# ultrasonic_send.net
KiCad netlist of a schematic drawn in EAGLE
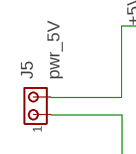
[diagram p0: schematic, sheet 1, part 1 of 2]
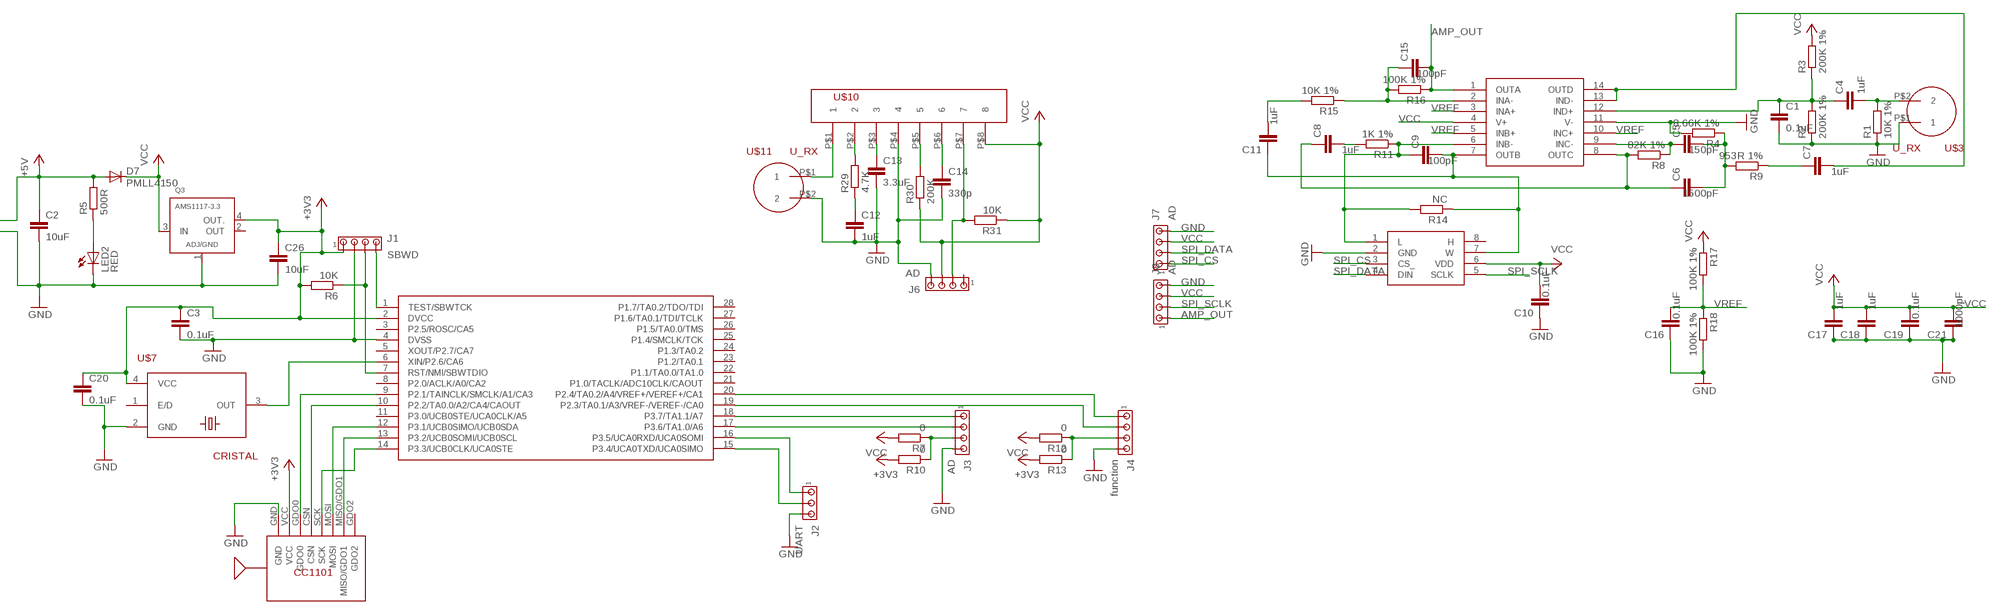
[diagram p1: schematic, sheet 1, part 2 of 2]

(export (version "E")
  (design (tool "Eeschema 10.0.6"))
  (components
    (comp (ref "C1")
      (value "0.1uF")
      (footprint "eagle-import:C0805")
      (libsource (lib "eagle-import") (part "C-EUC0805"))
    )
    (comp (ref "C2")
      (value "10uF")
      (footprint "eagle-import:C0805")
      (libsource (lib "eagle-import") (part "C-EUC0805"))
    )
    (comp (ref "C3")
      (value "0.1uF")
      (footprint "eagle-import:C0805")
      (libsource (lib "eagle-import") (part "C-EUC0805"))
    )
    (comp (ref "C4")
      (value "1uF")
      (footprint "eagle-import:C0805")
      (libsource (lib "eagle-import") (part "C-EUC0805"))
    )
    (comp (ref "C5")
      (value "150pF")
      (footprint "eagle-import:C0805")
      (libsource (lib "eagle-import") (part "C-EUC0805"))
    )
    (comp (ref "C6")
      (value "1500pF")
      (footprint "eagle-import:C0805")
      (libsource (lib "eagle-import") (part "C-EUC0805"))
    )
    (comp (ref "C7")
      (value "1uF")
      (footprint "eagle-import:C0805")
      (libsource (lib "eagle-import") (part "C-EUC0805"))
    )
    (comp (ref "C8")
      (value "1uF")
      (footprint "eagle-import:C0805")
      (libsource (lib "eagle-import") (part "C-EUC0805"))
    )
    (comp (ref "C9")
      (value "100pF")
      (footprint "eagle-import:C0805")
      (libsource (lib "eagle-import") (part "C-EUC0805"))
    )
    (comp (ref "C10")
      (value "0.1uF")
      (footprint "eagle-import:C0805")
      (libsource (lib "eagle-import") (part "C-EUC0805"))
    )
    (comp (ref "C11")
      (value "1uF")
      (footprint "eagle-import:C0805")
      (libsource (lib "eagle-import") (part "C-EUC0805"))
    )
    (comp (ref "C12")
      (value "1uF")
      (footprint "eagle-import:C0805")
      (libsource (lib "eagle-import") (part "C-EUC0805"))
    )
    (comp (ref "C13")
      (value "3.3uF")
      (footprint "eagle-import:C0805")
      (libsource (lib "eagle-import") (part "C-EUC0805"))
    )
    (comp (ref "C14")
      (value "330p")
      (footprint "eagle-import:C0805")
      (libsource (lib "eagle-import") (part "C-EUC0805"))
    )
    (comp (ref "C15")
      (value "100pF")
      (footprint "eagle-import:C0805")
      (libsource (lib "eagle-import") (part "C-EUC0805"))
    )
    (comp (ref "C16")
      (value "0.1uF")
      (footprint "eagle-import:C0805")
      (libsource (lib "eagle-import") (part "C-EUC0805"))
    )
    (comp (ref "C17")
      (value "1uF")
      (footprint "eagle-import:C0805")
      (libsource (lib "eagle-import") (part "C-EUC0805"))
    )
    (comp (ref "C18")
      (value "1uF")
      (footprint "eagle-import:C0805")
      (libsource (lib "eagle-import") (part "C-EUC0805"))
    )
    (comp (ref "C19")
      (value "0.1uF")
      (footprint "eagle-import:C0805")
      (libsource (lib "eagle-import") (part "C-EUC0805"))
    )
    (comp (ref "C20")
      (value "0.1uF")
      (footprint "eagle-import:C0805")
      (libsource (lib "eagle-import") (part "C-EUC0805"))
    )
    (comp (ref "C21")
      (value "1000pF")
      (footprint "eagle-import:C0805")
      (libsource (lib "eagle-import") (part "C-EUC0805"))
    )
    (comp (ref "C26")
      (value "10uF")
      (footprint "eagle-import:C0805")
      (libsource (lib "eagle-import") (part "C-EUC0805"))
    )
    (comp (ref "D7")
      (value "PMLL4150")
      (footprint "eagle-import:SOD80C")
      (libsource (lib "eagle-import") (part "PMLL4150"))
    )
    (comp (ref "J1")
      (value "SBWD")
      (footprint "eagle-import:10X04MTA")
      (libsource (lib "eagle-import") (part "MTA04-100"))
    )
    (comp (ref "J2")
      (value "UART")
      (footprint "eagle-import:10X03MTA")
      (libsource (lib "eagle-import") (part "MTA03-100"))
    )
    (comp (ref "J3")
      (value "AD")
      (footprint "eagle-import:10X04MTA")
      (libsource (lib "eagle-import") (part "MTA04-100"))
    )
    (comp (ref "J4")
      (value "function")
      (footprint "eagle-import:10X04MTA")
      (libsource (lib "eagle-import") (part "MTA04-100"))
    )
    (comp (ref "J5")
      (value "pwr_5V")
      (footprint "eagle-import:10X02MTA")
      (libsource (lib "eagle-import") (part "MTA02-100"))
    )
    (comp (ref "J6")
      (value "AD")
      (footprint "eagle-import:10X04MTA")
      (libsource (lib "eagle-import") (part "MTA04-100"))
    )
    (comp (ref "J7")
      (value "AD")
      (footprint "eagle-import:10X04MTA")
      (libsource (lib "eagle-import") (part "MTA04-100"))
    )
    (comp (ref "J8")
      (value "AD")
      (footprint "eagle-import:10X04MTA")
      (libsource (lib "eagle-import") (part "MTA04-100"))
    )
    (comp (ref "LED2")
      (value "RED")
      (footprint "eagle-import:SML0805")
      (libsource (lib "eagle-import") (part "LEDSML0805"))
    )
    (comp (ref "Q3")
      (value "AMS1117-3.3")
      (footprint "eagle-import:SOT223-4")
      (libsource (lib "eagle-import") (part "TLV1117"))
    )
    (comp (ref "R1")
      (value "10K 1%")
      (footprint "eagle-import:R0603")
      (libsource (lib "eagle-import") (part "R-EU_R0603"))
    )
    (comp (ref "R2")
      (value "200K 1%")
      (footprint "eagle-import:R0603")
      (libsource (lib "eagle-import") (part "R-EU_R0603"))
    )
    (comp (ref "R3")
      (value "200K 1%")
      (footprint "eagle-import:R0603")
      (libsource (lib "eagle-import") (part "R-EU_R0603"))
    )
    (comp (ref "R4")
      (value "8.66K 1%")
      (footprint "eagle-import:R0603")
      (libsource (lib "eagle-import") (part "R-EU_R0603"))
    )
    (comp (ref "R5")
      (value "500R")
      (footprint "eagle-import:R0603")
      (libsource (lib "eagle-import") (part "R-EU_R0603"))
    )
    (comp (ref "R6")
      (value "10K")
      (footprint "eagle-import:R0603")
      (libsource (lib "eagle-import") (part "R-EU_R0603"))
    )
    (comp (ref "R7")
      (value "0")
      (footprint "eagle-import:R0603")
      (libsource (lib "eagle-import") (part "R-EU_R0603"))
    )
    (comp (ref "R8")
      (value "82K 1%")
      (footprint "eagle-import:R0603")
      (libsource (lib "eagle-import") (part "R-EU_R0603"))
    )
    (comp (ref "R9")
      (value "953R 1%")
      (footprint "eagle-import:R0603")
      (libsource (lib "eagle-import") (part "R-EU_R0603"))
    )
    (comp (ref "R10")
      (value "0")
      (footprint "eagle-import:R0603")
      (libsource (lib "eagle-import") (part "R-EU_R0603"))
    )
    (comp (ref "R11")
      (value "1K 1%")
      (footprint "eagle-import:R0603")
      (libsource (lib "eagle-import") (part "R-EU_R0603"))
    )
    (comp (ref "R12")
      (value "0")
      (footprint "eagle-import:R0603")
      (libsource (lib "eagle-import") (part "R-EU_R0603"))
    )
    (comp (ref "R13")
      (value "0")
      (footprint "eagle-import:R0603")
      (libsource (lib "eagle-import") (part "R-EU_R0603"))
    )
    (comp (ref "R14")
      (value "NC")
      (footprint "eagle-import:R0603")
      (libsource (lib "eagle-import") (part "R-EU_R0603"))
    )
    (comp (ref "R15")
      (value "10K 1%")
      (footprint "eagle-import:R0603")
      (libsource (lib "eagle-import") (part "R-EU_R0603"))
    )
    (comp (ref "R16")
      (value "100K 1%")
      (footprint "eagle-import:R0603")
      (libsource (lib "eagle-import") (part "R-EU_R0603"))
    )
    (comp (ref "R17")
      (value "100K 1%")
      (footprint "eagle-import:R0603")
      (libsource (lib "eagle-import") (part "R-EU_R0603"))
    )
    (comp (ref "R18")
      (value "100K 1%")
      (footprint "eagle-import:R0603")
      (libsource (lib "eagle-import") (part "R-EU_R0603"))
    )
    (comp (ref "R29")
      (value "4.7K")
      (footprint "eagle-import:R0603")
      (libsource (lib "eagle-import") (part "R-EU_R0603"))
    )
    (comp (ref "R30")
      (value "200K")
      (footprint "eagle-import:R0603")
      (libsource (lib "eagle-import") (part "R-EU_R0603"))
    )
    (comp (ref "R31")
      (value "10K")
      (footprint "eagle-import:R0603")
      (libsource (lib "eagle-import") (part "R-EU_R0603"))
    )
    (comp (ref "U$1")
      (value "OPA1654PW")
      (footprint "eagle-import:D_R-PDSO-G14")
      (libsource (lib "eagle-import") (part "OPA1654PW"))
    )
    (comp (ref "U$2")
      (value "MSP430F2112")
      (footprint "eagle-import:PW_R-PDSO-G28")
      (libsource (lib "eagle-import") (part "MSP430F2112"))
    )
    (comp (ref "U$3")
      (value "U_RX")
      (footprint "eagle-import:ULTRASONIC")
      (libsource (lib "eagle-import") (part "ULTRASONIC"))
    )
    (comp (ref "U$4")
      (value "CC1101")
      (footprint "eagle-import:CC1101")
      (libsource (lib "eagle-import") (part "CC1101"))
    )
    (comp (ref "U$5")
      (value "MAX5401EKA-T")
      (footprint "eagle-import:SO08")
      (libsource (lib "eagle-import") (part "MAX5401EKA-T"))
    )
    (comp (ref "U$7")
      (value "CRISTAL")
      (footprint "eagle-import:CTS406")
      (libsource (lib "eagle-import") (part "CRISTAL"))
    )
    (comp (ref "U$10")
      (value "CX20106")
      (footprint "eagle-import:CX20106")
      (libsource (lib "eagle-import") (part "CX20106"))
    )
    (comp (ref "U$11")
      (value "U_RX")
      (footprint "eagle-import:ULTRASONIC")
      (libsource (lib "eagle-import") (part "ULTRASONIC"))
    )
  )
  (nets
    (net (code "1") (name "+3V3") (class "Default")
      (node (ref "C20") (pin "1") (pinfunction "1_1") (pintype "passive"))
      (node (ref "C26") (pin "1") (pinfunction "1_1") (pintype "passive"))
      (node (ref "C3") (pin "1") (pinfunction "1_1") (pintype "passive"))
      (node (ref "J1") (pin "1") (pinfunction "1_1") (pintype "passive"))
      (node (ref "Q3") (pin "4") (pinfunction "OUT._4") (pintype "power_in"))
      (node (ref "R10") (pin "2") (pinfunction "2_2") (pintype "passive"))
      (node (ref "R13") (pin "2") (pinfunction "2_2") (pintype "passive"))
      (node (ref "R6") (pin "2") (pinfunction "2_2") (pintype "passive"))
      (node (ref "U$2") (pin "2") (pinfunction "DVCC_2") (pintype "bidirectional"))
      (node (ref "U$4") (pin "VCC") (pinfunction "VCC_VCC") (pintype "bidirectional"))
      (node (ref "U$7") (pin "4") (pinfunction "VCC_4") (pintype "power_in"))
    )
    (net (code "2") (name "+5V") (class "Default")
      (node (ref "C2") (pin "1") (pinfunction "1_1") (pintype "passive"))
      (node (ref "D7") (pin "A") (pinfunction "A_A") (pintype "passive"))
      (node (ref "J5") (pin "2") (pinfunction "2_2") (pintype "passive"))
      (node (ref "R5") (pin "2") (pinfunction "2_2") (pintype "passive"))
    )
    (net (code "3") (name "/AMP_OUT") (class "Default")
      (node (ref "C15") (pin "2") (pinfunction "2_2") (pintype "passive"))
      (node (ref "J8") (pin "1") (pinfunction "1_1") (pintype "passive"))
      (node (ref "R16") (pin "1") (pinfunction "1_1") (pintype "passive"))
      (node (ref "U$1") (pin "1") (pinfunction "OUTA_1") (pintype "output"))
    )
    (net (code "4") (name "/OUT") (class "Default")
      (node (ref "Q3") (pin "2") (pinfunction "OUT_2") (pintype "power_in"))
    )
    (net (code "5") (name "/SPI_CS") (class "Default")
      (node (ref "J7") (pin "1") (pinfunction "1_1") (pintype "passive"))
      (node (ref "U$5") (pin "3") (pinfunction "CS__3") (pintype "bidirectional"))
    )
    (net (code "6") (name "/SPI_DATA") (class "Default")
      (node (ref "J7") (pin "2") (pinfunction "2_2") (pintype "passive"))
      (node (ref "U$5") (pin "4") (pinfunction "DIN_4") (pintype "bidirectional"))
    )
    (net (code "7") (name "/SPI_SCLK") (class "Default")
      (node (ref "J8") (pin "2") (pinfunction "2_2") (pintype "passive"))
      (node (ref "U$5") (pin "5") (pinfunction "SCLK_5") (pintype "input"))
    )
    (net (code "8") (name "/VREF") (class "Default")
      (node (ref "C16") (pin "2") (pinfunction "2_2") (pintype "passive"))
      (node (ref "R17") (pin "2") (pinfunction "2_2") (pintype "passive"))
      (node (ref "R18") (pin "1") (pinfunction "1_1") (pintype "passive"))
      (node (ref "U$1") (pin "10") (pinfunction "INC+_10") (pintype "input"))
      (node (ref "U$1") (pin "3") (pinfunction "INA+_3") (pintype "input"))
      (node (ref "U$1") (pin "5") (pinfunction "INB+_5") (pintype "input"))
    )
    (net (code "9") (name "GND") (class "Default")
      (node (ref "C1") (pin "2") (pinfunction "2_2") (pintype "passive"))
      (node (ref "C10") (pin "1") (pinfunction "1_1") (pintype "passive"))
      (node (ref "C12") (pin "2") (pinfunction "2_2") (pintype "passive"))
      (node (ref "C13") (pin "2") (pinfunction "2_2") (pintype "passive"))
      (node (ref "C14") (pin "2") (pinfunction "2_2") (pintype "passive"))
      (node (ref "C16") (pin "1") (pinfunction "1_1") (pintype "passive"))
      (node (ref "C17") (pin "1") (pinfunction "1_1") (pintype "passive"))
      (node (ref "C18") (pin "1") (pinfunction "1_1") (pintype "passive"))
      (node (ref "C19") (pin "1") (pinfunction "1_1") (pintype "passive"))
      (node (ref "C2") (pin "2") (pinfunction "2_2") (pintype "passive"))
      (node (ref "C20") (pin "2") (pinfunction "2_2") (pintype "passive"))
      (node (ref "C21") (pin "1") (pinfunction "1_1") (pintype "passive"))
      (node (ref "C26") (pin "2") (pinfunction "2_2") (pintype "passive"))
      (node (ref "C3") (pin "2") (pinfunction "2_2") (pintype "passive"))
      (node (ref "J1") (pin "2") (pinfunction "2_2") (pintype "passive"))
      (node (ref "J2") (pin "3") (pinfunction "3_3") (pintype "passive"))
      (node (ref "J3") (pin "4") (pinfunction "4_4") (pintype "passive"))
      (node (ref "J4") (pin "4") (pinfunction "4_4") (pintype "passive"))
      (node (ref "J5") (pin "1") (pinfunction "1_1") (pintype "passive"))
      (node (ref "J6") (pin "4") (pinfunction "4_4") (pintype "passive"))
      (node (ref "J7") (pin "4") (pinfunction "4_4") (pintype "passive"))
      (node (ref "J8") (pin "4") (pinfunction "4_4") (pintype "passive"))
      (node (ref "LED2") (pin "C") (pinfunction "C_C") (pintype "passive"))
      (node (ref "Q3") (pin "1") (pinfunction "ADJ/GND_1") (pintype "bidirectional"))
      (node (ref "R1") (pin "1") (pinfunction "1_1") (pintype "passive"))
      (node (ref "R18") (pin "2") (pinfunction "2_2") (pintype "passive"))
      (node (ref "R2") (pin "1") (pinfunction "1_1") (pintype "passive"))
      (node (ref "R4") (pin "2") (pinfunction "2_2") (pintype "passive"))
      (node (ref "U$1") (pin "11") (pinfunction "V-_11") (pintype "bidirectional"))
      (node (ref "U$10") (pin "P$4") (pinfunction "4_P$4") (pintype "bidirectional"))
      (node (ref "U$11") (pin "P$2") (pinfunction "2_P$2") (pintype "bidirectional"))
      (node (ref "U$2") (pin "4") (pinfunction "DVSS_4") (pintype "bidirectional"))
      (node (ref "U$3") (pin "P$1") (pinfunction "1_P$1") (pintype "bidirectional"))
      (node (ref "U$4") (pin "GND") (pinfunction "GND_GND") (pintype "bidirectional"))
      (node (ref "U$5") (pin "2") (pinfunction "GND_2") (pintype "bidirectional"))
      (node (ref "U$7") (pin "2") (pinfunction "GND_2") (pintype "power_in"))
    )
    (net (code "10") (name "Net-(C5-Pad2)") (class "Default")
      (node (ref "C5") (pin "2") (pinfunction "2_2") (pintype "passive"))
      (node (ref "C6") (pin "2") (pinfunction "2_2") (pintype "passive"))
      (node (ref "R4") (pin "1") (pinfunction "1_1") (pintype "passive"))
      (node (ref "R9") (pin "2") (pinfunction "2_2") (pintype "passive"))
    )
    (net (code "11") (name "Net-(C7-Pad1)") (class "Default")
      (node (ref "C7") (pin "1") (pinfunction "1_1") (pintype "passive"))
      (node (ref "R9") (pin "1") (pinfunction "1_1") (pintype "passive"))
    )
    (net (code "12") (name "Net-(C8-Pad2)") (class "Default")
      (node (ref "C8") (pin "2") (pinfunction "2_2") (pintype "passive"))
      (node (ref "R11") (pin "2") (pinfunction "2_2") (pintype "passive"))
    )
    (net (code "13") (name "Net-(C11-Pad2)") (class "Default")
      (node (ref "C11") (pin "2") (pinfunction "2_2") (pintype "passive"))
      (node (ref "R15") (pin "2") (pinfunction "2_2") (pintype "passive"))
    )
    (net (code "14") (name "Net-(C12-Pad1)") (class "Default")
      (node (ref "C12") (pin "1") (pinfunction "1_1") (pintype "passive"))
      (node (ref "R29") (pin "1") (pinfunction "1_1") (pintype "passive"))
    )
    (net (code "15") (name "Net-(J3-Pad3)") (class "Default")
      (node (ref "J3") (pin "3") (pinfunction "3_3") (pintype "passive"))
      (node (ref "R10") (pin "1") (pinfunction "1_1") (pintype "passive"))
      (node (ref "R7") (pin "1") (pinfunction "1_1") (pintype "passive"))
    )
    (net (code "16") (name "Net-(J4-Pad3)") (class "Default")
      (node (ref "J4") (pin "3") (pinfunction "3_3") (pintype "passive"))
      (node (ref "R12") (pin "1") (pinfunction "1_1") (pintype "passive"))
      (node (ref "R13") (pin "1") (pinfunction "1_1") (pintype "passive"))
    )
    (net (code "17") (name "Net-(LED2-PadA)") (class "Default")
      (node (ref "LED2") (pin "A") (pinfunction "A_A") (pintype "passive"))
      (node (ref "R5") (pin "1") (pinfunction "1_1") (pintype "passive"))
    )
    (net (code "18") (name "Net-(U$1-INA-)") (class "Default")
      (node (ref "C15") (pin "1") (pinfunction "1_1") (pintype "passive"))
      (node (ref "R15") (pin "1") (pinfunction "1_1") (pintype "passive"))
      (node (ref "R16") (pin "2") (pinfunction "2_2") (pintype "passive"))
      (node (ref "U$1") (pin "2") (pinfunction "INA-_2") (pintype "input"))
    )
    (net (code "19") (name "Net-(U$1-INB-)") (class "Default")
      (node (ref "C9") (pin "1") (pinfunction "1_1") (pintype "passive"))
      (node (ref "R11") (pin "1") (pinfunction "1_1") (pintype "passive"))
      (node (ref "R14") (pin "2") (pinfunction "2_2") (pintype "passive"))
      (node (ref "U$1") (pin "6") (pinfunction "INB-_6") (pintype "input"))
      (node (ref "U$5") (pin "1") (pinfunction "L_1") (pintype "bidirectional"))
    )
    (net (code "20") (name "Net-(U$1-INC-)") (class "Default")
      (node (ref "C5") (pin "1") (pinfunction "1_1") (pintype "passive"))
      (node (ref "R8") (pin "1") (pinfunction "1_1") (pintype "passive"))
      (node (ref "U$1") (pin "9") (pinfunction "INC-_9") (pintype "input"))
    )
    (net (code "21") (name "Net-(U$1-IND+)") (class "Default")
      (node (ref "C1") (pin "1") (pinfunction "1_1") (pintype "passive"))
      (node (ref "C4") (pin "1") (pinfunction "1_1") (pintype "passive"))
      (node (ref "R2") (pin "2") (pinfunction "2_2") (pintype "passive"))
      (node (ref "R3") (pin "1") (pinfunction "1_1") (pintype "passive"))
      (node (ref "U$1") (pin "12") (pinfunction "IND+_12") (pintype "input"))
    )
    (net (code "22") (name "Net-(U$1-IND-)") (class "Default")
      (node (ref "C7") (pin "2") (pinfunction "2_2") (pintype "passive"))
      (node (ref "U$1") (pin "13") (pinfunction "IND-_13") (pintype "input"))
      (node (ref "U$1") (pin "14") (pinfunction "OUTD_14") (pintype "output"))
    )
    (net (code "23") (name "Net-(U$1-OUTB)") (class "Default")
      (node (ref "C11") (pin "1") (pinfunction "1_1") (pintype "passive"))
      (node (ref "C9") (pin "2") (pinfunction "2_2") (pintype "passive"))
      (node (ref "R14") (pin "1") (pinfunction "1_1") (pintype "passive"))
      (node (ref "U$1") (pin "7") (pinfunction "OUTB_7") (pintype "output"))
      (node (ref "U$5") (pin "7") (pinfunction "W_7") (pintype "bidirectional"))
    )
    (net (code "24") (name "Net-(U$1-OUTC)") (class "Default")
      (node (ref "C6") (pin "1") (pinfunction "1_1") (pintype "passive"))
      (node (ref "C8") (pin "1") (pinfunction "1_1") (pintype "passive"))
      (node (ref "R8") (pin "2") (pinfunction "2_2") (pintype "passive"))
      (node (ref "U$1") (pin "8") (pinfunction "OUTC_8") (pintype "output"))
    )
    (net (code "25") (name "Net-(U$2-P2.1{slash}TAINCLK{slash}SMCLK{slash}A1{slash}CA3)") (class "Default")
      (node (ref "U$2") (pin "9") (pinfunction "P2.1/TAINCLK/SMCLK/A1/CA3_9") (pintype "bidirectional"))
      (node (ref "U$4") (pin "GDO0") (pinfunction "GDO0_GDO0") (pintype "bidirectional"))
    )
    (net (code "26") (name "Net-(U$2-P2.2{slash}TA0.0{slash}A2{slash}CA4{slash}CAOUT)") (class "Default")
      (node (ref "U$2") (pin "10") (pinfunction "P2.2/TA0.0/A2/CA4/CAOUT_10") (pintype "bidirectional"))
      (node (ref "U$4") (pin "CSN") (pinfunction "CSN_CSN") (pintype "bidirectional"))
    )
    (net (code "27") (name "Net-(U$2-P2.3{slash}TA0.1{slash}A3{slash}VREF-{slash}VEREF-{slash}CA0)") (class "Default")
      (node (ref "J4") (pin "2") (pinfunction "2_2") (pintype "passive"))
      (node (ref "U$2") (pin "19") (pinfunction "P2.3/TA0.1/A3/VREF-/VEREF-/CA0_19") (pintype "bidirectional"))
    )
    (net (code "28") (name "Net-(U$2-P2.4{slash}TA0.2{slash}A4{slash}VREF+{slash}VEREF+{slash}CA1)") (class "Default")
      (node (ref "J4") (pin "1") (pinfunction "1_1") (pintype "passive"))
      (node (ref "U$2") (pin "20") (pinfunction "P2.4/TA0.2/A4/VREF+/VEREF+/CA1_20") (pintype "bidirectional"))
    )
    (net (code "29") (name "Net-(U$2-P3.1{slash}UCB0SIMO{slash}UCB0SDA)") (class "Default")
      (node (ref "U$2") (pin "12") (pinfunction "P3.1/UCB0SIMO/UCB0SDA_12") (pintype "bidirectional"))
      (node (ref "U$4") (pin "MOSI") (pinfunction "MOSI_MOSI") (pintype "bidirectional"))
    )
    (net (code "30") (name "Net-(U$2-P3.2{slash}UCB0SOMI{slash}UCB0SCL)") (class "Default")
      (node (ref "U$2") (pin "13") (pinfunction "P3.2/UCB0SOMI/UCB0SCL_13") (pintype "bidirectional"))
      (node (ref "U$4") (pin "MISO/GDO1") (pinfunction "MISO/GDO1_MISO/GDO1") (pintype "bidirectional"))
    )
    (net (code "31") (name "Net-(U$2-P3.3{slash}UCB0CLK{slash}UCA0STE)") (class "Default")
      (node (ref "U$2") (pin "14") (pinfunction "P3.3/UCB0CLK/UCA0STE_14") (pintype "bidirectional"))
      (node (ref "U$4") (pin "SCK") (pinfunction "SCK_SCK") (pintype "bidirectional"))
    )
    (net (code "32") (name "Net-(U$2-P3.4{slash}UCA0TXD{slash}UCA0SIMO)") (class "Default")
      (node (ref "J2") (pin "2") (pinfunction "2_2") (pintype "passive"))
      (node (ref "U$2") (pin "15") (pinfunction "P3.4/UCA0TXD/UCA0SIMO_15") (pintype "bidirectional"))
    )
    (net (code "33") (name "Net-(U$2-P3.5{slash}UCA0RXD{slash}UCA0SOMI)") (class "Default")
      (node (ref "J2") (pin "1") (pinfunction "1_1") (pintype "passive"))
      (node (ref "U$2") (pin "16") (pinfunction "P3.5/UCA0RXD/UCA0SOMI_16") (pintype "bidirectional"))
    )
    (net (code "34") (name "Net-(U$2-P3.6{slash}TA1.0{slash}A6)") (class "Default")
      (node (ref "J3") (pin "2") (pinfunction "2_2") (pintype "passive"))
      (node (ref "U$2") (pin "17") (pinfunction "P3.6/TA1.0/A6_17") (pintype "bidirectional"))
    )
    (net (code "35") (name "Net-(U$2-P3.7{slash}TA1.1{slash}A7)") (class "Default")
      (node (ref "J3") (pin "1") (pinfunction "1_1") (pintype "passive"))
      (node (ref "U$2") (pin "18") (pinfunction "P3.7/TA1.1/A7_18") (pintype "bidirectional"))
    )
    (net (code "36") (name "Net-(U$2-RST{slash}NMI{slash}SBWTDIO)") (class "Default")
      (node (ref "J1") (pin "3") (pinfunction "3_3") (pintype "passive"))
      (node (ref "R6") (pin "1") (pinfunction "1_1") (pintype "passive"))
      (node (ref "U$2") (pin "7") (pinfunction "RST/NMI/SBWTDIO_7") (pintype "bidirectional"))
    )
    (net (code "37") (name "Net-(U$2-TEST{slash}SBWTCK)") (class "Default")
      (node (ref "J1") (pin "4") (pinfunction "4_4") (pintype "passive"))
      (node (ref "U$2") (pin "1") (pinfunction "TEST/SBWTCK_1") (pintype "bidirectional"))
    )
    (net (code "38") (name "Net-(U$2-XIN{slash}P2.6{slash}CA6)") (class "Default")
      (node (ref "U$2") (pin "6") (pinfunction "XIN/P2.6/CA6_6") (pintype "bidirectional"))
      (node (ref "U$7") (pin "3") (pinfunction "OUT_3") (pintype "output"))
    )
    (net (code "39") (name "Net-(U$3-2)") (class "Default")
      (node (ref "C4") (pin "2") (pinfunction "2_2") (pintype "passive"))
      (node (ref "R1") (pin "2") (pinfunction "2_2") (pintype "passive"))
      (node (ref "U$3") (pin "P$2") (pinfunction "2_P$2") (pintype "bidirectional"))
    )
    (net (code "40") (name "Net-(U$10-1)") (class "Default")
      (node (ref "U$10") (pin "P$1") (pinfunction "1_P$1") (pintype "bidirectional"))
      (node (ref "U$11") (pin "P$1") (pinfunction "1_P$1") (pintype "bidirectional"))
    )
    (net (code "41") (name "Net-(U$10-2)") (class "Default")
      (node (ref "R29") (pin "2") (pinfunction "2_2") (pintype "passive"))
      (node (ref "U$10") (pin "P$2") (pinfunction "2_P$2") (pintype "bidirectional"))
    )
    (net (code "42") (name "Net-(U$10-3)") (class "Default")
      (node (ref "C13") (pin "1") (pinfunction "1_1") (pintype "passive"))
      (node (ref "U$10") (pin "P$3") (pinfunction "3_P$3") (pintype "bidirectional"))
    )
    (net (code "43") (name "Net-(U$10-5)") (class "Default")
      (node (ref "R30") (pin "2") (pinfunction "2_2") (pintype "passive"))
      (node (ref "U$10") (pin "P$5") (pinfunction "5_P$5") (pintype "bidirectional"))
    )
    (net (code "44") (name "Net-(U$10-6)") (class "Default")
      (node (ref "C14") (pin "1") (pinfunction "1_1") (pintype "passive"))
      (node (ref "U$10") (pin "P$6") (pinfunction "6_P$6") (pintype "bidirectional"))
    )
    (net (code "45") (name "Net-(U$10-7)") (class "Default")
      (node (ref "J6") (pin "2") (pinfunction "2_2") (pintype "passive"))
      (node (ref "R31") (pin "2") (pinfunction "2_2") (pintype "passive"))
      (node (ref "U$10") (pin "P$7") (pinfunction "7_P$7") (pintype "bidirectional"))
    )
    (net (code "46") (name "VCC") (class "Default")
      (node (ref "C10") (pin "2") (pinfunction "2_2") (pintype "passive"))
      (node (ref "C17") (pin "2") (pinfunction "2_2") (pintype "passive"))
      (node (ref "C18") (pin "2") (pinfunction "2_2") (pintype "passive"))
      (node (ref "C19") (pin "2") (pinfunction "2_2") (pintype "passive"))
      (node (ref "C21") (pin "2") (pinfunction "2_2") (pintype "passive"))
      (node (ref "D7") (pin "C") (pinfunction "C_C") (pintype "passive"))
      (node (ref "J6") (pin "3") (pinfunction "3_3") (pintype "passive"))
      (node (ref "J7") (pin "3") (pinfunction "3_3") (pintype "passive"))
      (node (ref "J8") (pin "3") (pinfunction "3_3") (pintype "passive"))
      (node (ref "Q3") (pin "3") (pinfunction "IN_3") (pintype "power_in"))
      (node (ref "R12") (pin "2") (pinfunction "2_2") (pintype "passive"))
      (node (ref "R17") (pin "1") (pinfunction "1_1") (pintype "passive"))
      (node (ref "R3") (pin "2") (pinfunction "2_2") (pintype "passive"))
      (node (ref "R30") (pin "1") (pinfunction "1_1") (pintype "passive"))
      (node (ref "R31") (pin "1") (pinfunction "1_1") (pintype "passive"))
      (node (ref "R7") (pin "2") (pinfunction "2_2") (pintype "passive"))
      (node (ref "U$1") (pin "4") (pinfunction "V+_4") (pintype "bidirectional"))
      (node (ref "U$10") (pin "P$8") (pinfunction "8_P$8") (pintype "bidirectional"))
      (node (ref "U$5") (pin "6") (pinfunction "VDD_6") (pintype "bidirectional"))
    )
    (net (code "47") (name "unconnected-(J6-Pad1)") (class "Default")
      (node (ref "J6") (pin "1") (pinfunction "1_1") (pintype "passive"))
    )
    (net (code "48") (name "unconnected-(U$2-P1.0{slash}TACLK{slash}ADC10CLK{slash}CAOUT-Pad21)") (class "Default")
      (node (ref "U$2") (pin "21") (pinfunction "P1.0/TACLK/ADC10CLK/CAOUT_21") (pintype "bidirectional"))
    )
    (net (code "49") (name "unconnected-(U$2-P1.1{slash}TA0.0{slash}TA1.0-Pad22)") (class "Default")
      (node (ref "U$2") (pin "22") (pinfunction "P1.1/TA0.0/TA1.0_22") (pintype "bidirectional"))
    )
    (net (code "50") (name "unconnected-(U$2-P1.2{slash}TA0.1-Pad23)") (class "Default")
      (node (ref "U$2") (pin "23") (pinfunction "P1.2/TA0.1_23") (pintype "bidirectional"))
    )
    (net (code "51") (name "unconnected-(U$2-P1.3{slash}TA0.2-Pad24)") (class "Default")
      (node (ref "U$2") (pin "24") (pinfunction "P1.3/TA0.2_24") (pintype "bidirectional"))
    )
    (net (code "52") (name "unconnected-(U$2-P1.4{slash}SMCLK{slash}TCK-Pad25)") (class "Default")
      (node (ref "U$2") (pin "25") (pinfunction "P1.4/SMCLK/TCK_25") (pintype "bidirectional"))
    )
    (net (code "53") (name "unconnected-(U$2-P1.5{slash}TA0.0{slash}TMS-Pad26)") (class "Default")
      (node (ref "U$2") (pin "26") (pinfunction "P1.5/TA0.0/TMS_26") (pintype "bidirectional"))
    )
    (net (code "54") (name "unconnected-(U$2-P1.6{slash}TA0.1{slash}TDI{slash}TCLK-Pad27)") (class "Default")
      (node (ref "U$2") (pin "27") (pinfunction "P1.6/TA0.1/TDI/TCLK_27") (pintype "bidirectional"))
    )
    (net (code "55") (name "unconnected-(U$2-P1.7{slash}TA0.2{slash}TDO{slash}TDI-Pad28)") (class "Default")
      (node (ref "U$2") (pin "28") (pinfunction "P1.7/TA0.2/TDO/TDI_28") (pintype "bidirectional"))
    )
    (net (code "56") (name "unconnected-(U$2-P2.0{slash}ACLK{slash}A0{slash}CA2-Pad8)") (class "Default")
      (node (ref "U$2") (pin "8") (pinfunction "P2.0/ACLK/A0/CA2_8") (pintype "bidirectional"))
    )
    (net (code "57") (name "unconnected-(U$2-P2.5{slash}ROSC{slash}CA5-Pad3)") (class "Default")
      (node (ref "U$2") (pin "3") (pinfunction "P2.5/ROSC/CA5_3") (pintype "bidirectional"))
    )
    (net (code "58") (name "unconnected-(U$2-P3.0{slash}UCB0STE{slash}UCA0CLK{slash}A5-Pad11)") (class "Default")
      (node (ref "U$2") (pin "11") (pinfunction "P3.0/UCB0STE/UCA0CLK/A5_11") (pintype "bidirectional"))
    )
    (net (code "59") (name "unconnected-(U$2-XOUT{slash}P2.7{slash}CA7-Pad5)") (class "Default")
      (node (ref "U$2") (pin "5") (pinfunction "XOUT/P2.7/CA7_5") (pintype "bidirectional"))
    )
    (net (code "60") (name "unconnected-(U$4-PadGDO2)") (class "Default")
      (node (ref "U$4") (pin "GDO2") (pinfunction "GDO2_GDO2") (pintype "bidirectional"))
    )
    (net (code "61") (name "unconnected-(U$5-H-Pad8)") (class "Default")
      (node (ref "U$5") (pin "8") (pinfunction "H_8") (pintype "bidirectional"))
    )
    (net (code "62") (name "unconnected-(U$7-E{slash}D-Pad1)") (class "Default")
      (node (ref "U$7") (pin "1") (pinfunction "E/D_1") (pintype "no_connect"))
    )
  )
)
